# digital_interface_1_1.net
KiCad netlist of a schematic drawn in EAGLE
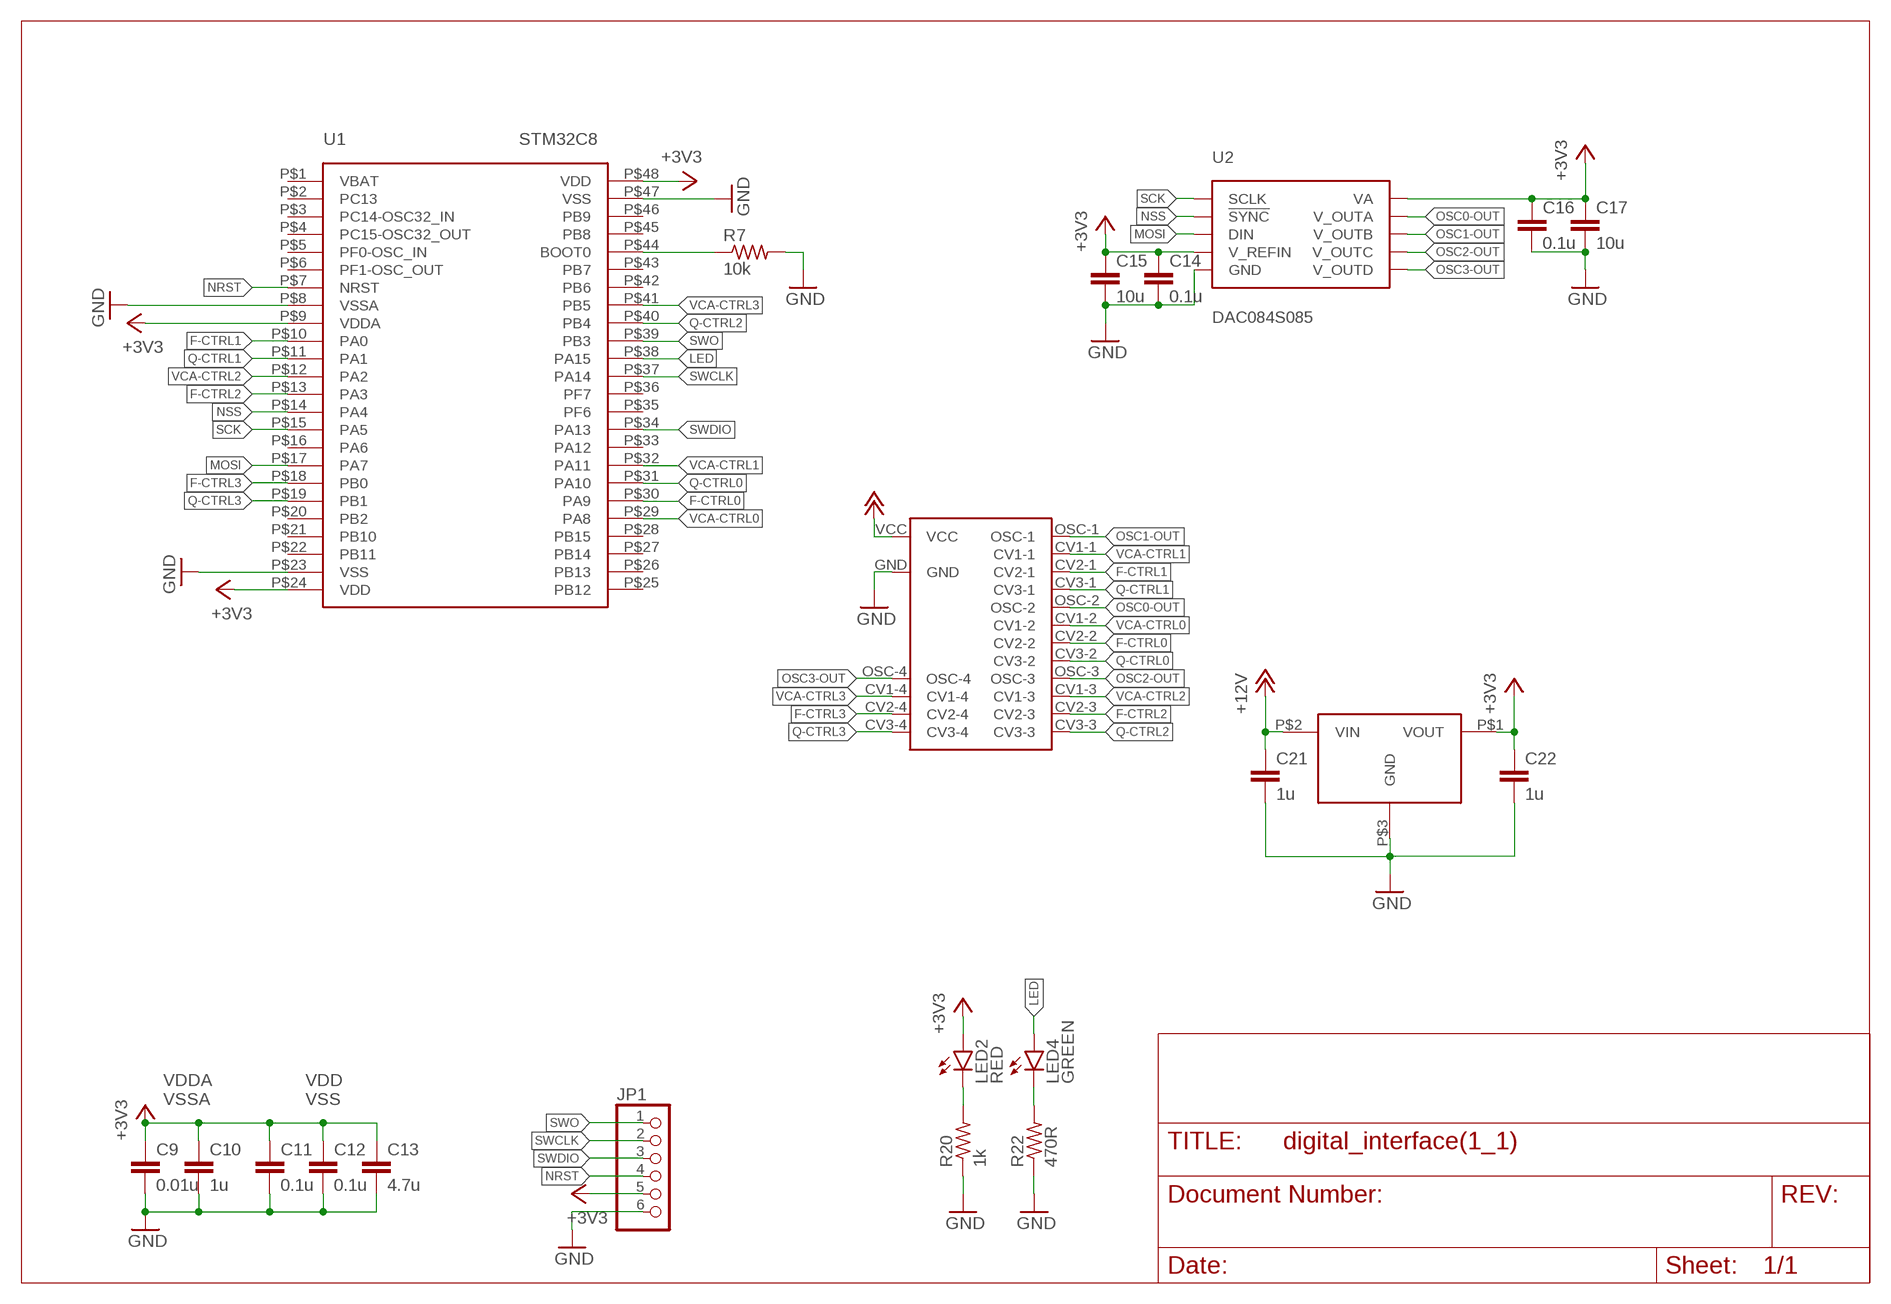
[diagram p0: schematic, sheet 1]

(export (version "E")
  (design (tool "Eeschema 10.0.6"))
  (components
    (comp (ref "C9")
      (value "0.01u")
      (footprint "eagle-import:C0603")
      (libsource (lib "eagle-import") (part "C-EUC0603"))
    )
    (comp (ref "C10")
      (value "1u")
      (footprint "eagle-import:C0603")
      (libsource (lib "eagle-import") (part "C-EUC0603"))
    )
    (comp (ref "C11")
      (value "0.1u")
      (footprint "eagle-import:C0603")
      (libsource (lib "eagle-import") (part "C-EUC0603"))
    )
    (comp (ref "C12")
      (value "0.1u")
      (footprint "eagle-import:C0603")
      (libsource (lib "eagle-import") (part "C-EUC0603"))
    )
    (comp (ref "C13")
      (value "4.7u")
      (footprint "eagle-import:C0603")
      (libsource (lib "eagle-import") (part "C-EUC0603"))
    )
    (comp (ref "C14")
      (value "0.1u")
      (footprint "eagle-import:C0603")
      (libsource (lib "eagle-import") (part "C-EUC0603"))
    )
    (comp (ref "C15")
      (value "10u")
      (footprint "eagle-import:C0603")
      (libsource (lib "eagle-import") (part "C-EUC0603"))
    )
    (comp (ref "C16")
      (value "0.1u")
      (footprint "eagle-import:C0603")
      (libsource (lib "eagle-import") (part "C-EUC0603"))
    )
    (comp (ref "C17")
      (value "10u")
      (footprint "eagle-import:C0603")
      (libsource (lib "eagle-import") (part "C-EUC0603"))
    )
    (comp (ref "C21")
      (value "1u")
      (footprint "eagle-import:C0603")
      (libsource (lib "eagle-import") (part "C-EUC0603"))
    )
    (comp (ref "C22")
      (value "1u")
      (footprint "eagle-import:C0603")
      (libsource (lib "eagle-import") (part "C-EUC0603"))
    )
    (comp (ref "JP1")
      (value "PINHD-1X6")
      (footprint "eagle-import:1X06")
      (libsource (lib "eagle-import") (part "PINHD-1X6"))
    )
    (comp (ref "LED2")
      (value "RED")
      (footprint "eagle-import:1206")
      (libsource (lib "eagle-import") (part "LEDSMT1206"))
    )
    (comp (ref "LED4")
      (value "GREEN")
      (footprint "eagle-import:1206")
      (libsource (lib "eagle-import") (part "LEDSMT1206"))
    )
    (comp (ref "R7")
      (value "10k")
      (footprint "eagle-import:R0603")
      (libsource (lib "eagle-import") (part "R-US_R0603"))
    )
    (comp (ref "R20")
      (value "1k")
      (footprint "eagle-import:R0603")
      (libsource (lib "eagle-import") (part "R-US_R0603"))
    )
    (comp (ref "R22")
      (value "470R")
      (footprint "eagle-import:R0603")
      (libsource (lib "eagle-import") (part "R-US_R0603"))
    )
    (comp (ref "U$1")
      (value "CV_MODULE")
      (footprint "eagle-import:CV_MODULE")
      (libsource (lib "eagle-import") (part "CV_MODULE"))
    )
    (comp (ref "U1")
      (value "STM32C8")
      (footprint "eagle-import:LQFP48")
      (libsource (lib "eagle-import") (part "STM32C8"))
    )
    (comp (ref "U2")
      (value "DAC084S085")
      (footprint "eagle-import:VSSOP10")
      (libsource (lib "eagle-import") (part "DAC084S085"))
    )
    (comp (ref "U3")
      (value "TLV760")
      (footprint "eagle-import:SOT23-3")
      (libsource (lib "eagle-import") (part "TLV760"))
    )
  )
  (nets
    (net (code "1") (name "+3V3") (class "Default")
      (node (ref "C10") (pin "1") (pinfunction "1_1") (pintype "passive"))
      (node (ref "C11") (pin "1") (pinfunction "1_1") (pintype "passive"))
      (node (ref "C12") (pin "1") (pinfunction "1_1") (pintype "passive"))
      (node (ref "C13") (pin "1") (pinfunction "1_1") (pintype "passive"))
      (node (ref "C14") (pin "1") (pinfunction "1_1") (pintype "passive"))
      (node (ref "C15") (pin "1") (pinfunction "1_1") (pintype "passive"))
      (node (ref "C16") (pin "1") (pinfunction "1_1") (pintype "passive"))
      (node (ref "C17") (pin "1") (pinfunction "1_1") (pintype "passive"))
      (node (ref "C22") (pin "1") (pinfunction "1_1") (pintype "passive"))
      (node (ref "C9") (pin "1") (pinfunction "1_1") (pintype "passive"))
      (node (ref "JP1") (pin "5") (pinfunction "5_5") (pintype "passive"))
      (node (ref "LED2") (pin "A") (pinfunction "A_A") (pintype "passive"))
      (node (ref "U1") (pin "P$24") (pinfunction "VDD_P$24") (pintype "bidirectional"))
      (node (ref "U1") (pin "P$48") (pinfunction "VDD_P$48") (pintype "bidirectional"))
      (node (ref "U1") (pin "P$9") (pinfunction "VDDA_P$9") (pintype "bidirectional"))
      (node (ref "U2") (pin "P$1") (pinfunction "VA_P$1") (pintype "bidirectional"))
      (node (ref "U2") (pin "P$7") (pinfunction "V_REFIN_P$7") (pintype "bidirectional"))
      (node (ref "U3") (pin "P$1") (pinfunction "VOUT_P$1") (pintype "bidirectional"))
    )
    (net (code "2") (name "+12V") (class "Default")
      (node (ref "C21") (pin "1") (pinfunction "1_1") (pintype "passive"))
      (node (ref "U$1") (pin "VCC") (pinfunction "VCC_VCC") (pintype "bidirectional"))
      (node (ref "U3") (pin "P$2") (pinfunction "VIN_P$2") (pintype "bidirectional"))
    )
    (net (code "3") (name "F-CTRL0") (class "Default")
      (node (ref "U$1") (pin "CV2-2") (pinfunction "CV2-2_CV2-2") (pintype "bidirectional"))
      (node (ref "U1") (pin "P$30") (pinfunction "PA9_P$30") (pintype "bidirectional"))
    )
    (net (code "4") (name "F-CTRL1") (class "Default")
      (node (ref "U$1") (pin "CV2-1") (pinfunction "CV2-1_CV2-1") (pintype "bidirectional"))
      (node (ref "U1") (pin "P$10") (pinfunction "PA0_P$10") (pintype "bidirectional"))
    )
    (net (code "5") (name "F-CTRL2") (class "Default")
      (node (ref "U$1") (pin "CV2-3") (pinfunction "CV2-3_CV2-3") (pintype "bidirectional"))
      (node (ref "U1") (pin "P$13") (pinfunction "PA3_P$13") (pintype "bidirectional"))
    )
    (net (code "6") (name "F-CTRL3") (class "Default")
      (node (ref "U$1") (pin "CV2-4") (pinfunction "CV2-4_CV2-4") (pintype "bidirectional"))
      (node (ref "U1") (pin "P$18") (pinfunction "PB0_P$18") (pintype "bidirectional"))
    )
    (net (code "7") (name "GND") (class "Default")
      (node (ref "C10") (pin "2") (pinfunction "2_2") (pintype "passive"))
      (node (ref "C11") (pin "2") (pinfunction "2_2") (pintype "passive"))
      (node (ref "C12") (pin "2") (pinfunction "2_2") (pintype "passive"))
      (node (ref "C13") (pin "2") (pinfunction "2_2") (pintype "passive"))
      (node (ref "C14") (pin "2") (pinfunction "2_2") (pintype "passive"))
      (node (ref "C15") (pin "2") (pinfunction "2_2") (pintype "passive"))
      (node (ref "C16") (pin "2") (pinfunction "2_2") (pintype "passive"))
      (node (ref "C17") (pin "2") (pinfunction "2_2") (pintype "passive"))
      (node (ref "C21") (pin "2") (pinfunction "2_2") (pintype "passive"))
      (node (ref "C22") (pin "2") (pinfunction "2_2") (pintype "passive"))
      (node (ref "C9") (pin "2") (pinfunction "2_2") (pintype "passive"))
      (node (ref "JP1") (pin "6") (pinfunction "6_6") (pintype "passive"))
      (node (ref "R20") (pin "1") (pinfunction "1_1") (pintype "passive"))
      (node (ref "R22") (pin "1") (pinfunction "1_1") (pintype "passive"))
      (node (ref "R7") (pin "2") (pinfunction "2_2") (pintype "passive"))
      (node (ref "U$1") (pin "GND") (pinfunction "GND_GND") (pintype "bidirectional"))
      (node (ref "U1") (pin "P$23") (pinfunction "VSS_P$23") (pintype "bidirectional"))
      (node (ref "U1") (pin "P$47") (pinfunction "VSS_P$47") (pintype "bidirectional"))
      (node (ref "U1") (pin "P$8") (pinfunction "VSSA_P$8") (pintype "bidirectional"))
      (node (ref "U2") (pin "P$6") (pinfunction "GND_P$6") (pintype "bidirectional"))
      (node (ref "U3") (pin "P$3") (pinfunction "GND_P$3") (pintype "bidirectional"))
    )
    (net (code "8") (name "LED") (class "Default")
      (node (ref "LED4") (pin "A") (pinfunction "A_A") (pintype "passive"))
      (node (ref "U1") (pin "P$38") (pinfunction "PA15_P$38") (pintype "bidirectional"))
    )
    (net (code "9") (name "MOSI") (class "Default")
      (node (ref "U1") (pin "P$17") (pinfunction "PA7_P$17") (pintype "bidirectional"))
      (node (ref "U2") (pin "P$8") (pinfunction "DIN_P$8") (pintype "bidirectional"))
    )
    (net (code "10") (name "NRST") (class "Default")
      (node (ref "JP1") (pin "4") (pinfunction "4_4") (pintype "passive"))
      (node (ref "U1") (pin "P$7") (pinfunction "NRST_P$7") (pintype "bidirectional"))
    )
    (net (code "11") (name "NSS") (class "Default")
      (node (ref "U1") (pin "P$14") (pinfunction "PA4_P$14") (pintype "bidirectional"))
      (node (ref "U2") (pin "P$9") (pinfunction "~{SYNC}_P$9") (pintype "bidirectional"))
    )
    (net (code "12") (name "Net-(LED2-PadC)") (class "Default")
      (node (ref "LED2") (pin "C") (pinfunction "C_C") (pintype "passive"))
      (node (ref "R20") (pin "2") (pinfunction "2_2") (pintype "passive"))
    )
    (net (code "13") (name "Net-(LED4-PadC)") (class "Default")
      (node (ref "LED4") (pin "C") (pinfunction "C_C") (pintype "passive"))
      (node (ref "R22") (pin "2") (pinfunction "2_2") (pintype "passive"))
    )
    (net (code "14") (name "Net-(U1-BOOT0)") (class "Default")
      (node (ref "R7") (pin "1") (pinfunction "1_1") (pintype "passive"))
      (node (ref "U1") (pin "P$44") (pinfunction "BOOT0_P$44") (pintype "bidirectional"))
    )
    (net (code "15") (name "OSC0-OUT") (class "Default")
      (node (ref "U$1") (pin "OSC-2") (pinfunction "OSC-2_OSC-2") (pintype "bidirectional"))
      (node (ref "U2") (pin "P$2") (pinfunction "V_OUTA_P$2") (pintype "bidirectional"))
    )
    (net (code "16") (name "OSC1-OUT") (class "Default")
      (node (ref "U$1") (pin "OSC-1") (pinfunction "OSC-1_OSC-1") (pintype "bidirectional"))
      (node (ref "U2") (pin "P$3") (pinfunction "V_OUTB_P$3") (pintype "bidirectional"))
    )
    (net (code "17") (name "OSC2-OUT") (class "Default")
      (node (ref "U$1") (pin "OSC-3") (pinfunction "OSC-3_OSC-3") (pintype "bidirectional"))
      (node (ref "U2") (pin "P$4") (pinfunction "V_OUTC_P$4") (pintype "bidirectional"))
    )
    (net (code "18") (name "OSC3-OUT") (class "Default")
      (node (ref "U$1") (pin "OSC-4") (pinfunction "OSC-4_OSC-4") (pintype "bidirectional"))
      (node (ref "U2") (pin "P$5") (pinfunction "V_OUTD_P$5") (pintype "bidirectional"))
    )
    (net (code "19") (name "Q-CTRL0") (class "Default")
      (node (ref "U$1") (pin "CV3-2") (pinfunction "CV3-2_CV3-2") (pintype "bidirectional"))
      (node (ref "U1") (pin "P$31") (pinfunction "PA10_P$31") (pintype "bidirectional"))
    )
    (net (code "20") (name "Q-CTRL1") (class "Default")
      (node (ref "U$1") (pin "CV3-1") (pinfunction "CV3-1_CV3-1") (pintype "bidirectional"))
      (node (ref "U1") (pin "P$11") (pinfunction "PA1_P$11") (pintype "bidirectional"))
    )
    (net (code "21") (name "Q-CTRL2") (class "Default")
      (node (ref "U$1") (pin "CV3-3") (pinfunction "CV3-3_CV3-3") (pintype "bidirectional"))
      (node (ref "U1") (pin "P$40") (pinfunction "PB4_P$40") (pintype "bidirectional"))
    )
    (net (code "22") (name "Q-CTRL3") (class "Default")
      (node (ref "U$1") (pin "CV3-4") (pinfunction "CV3-4_CV3-4") (pintype "bidirectional"))
      (node (ref "U1") (pin "P$19") (pinfunction "PB1_P$19") (pintype "bidirectional"))
    )
    (net (code "23") (name "SCK") (class "Default")
      (node (ref "U1") (pin "P$15") (pinfunction "PA5_P$15") (pintype "bidirectional"))
      (node (ref "U2") (pin "P$10") (pinfunction "SCLK_P$10") (pintype "bidirectional"))
    )
    (net (code "24") (name "SWCLK") (class "Default")
      (node (ref "JP1") (pin "2") (pinfunction "2_2") (pintype "passive"))
      (node (ref "U1") (pin "P$37") (pinfunction "PA14_P$37") (pintype "bidirectional"))
    )
    (net (code "25") (name "SWDIO") (class "Default")
      (node (ref "JP1") (pin "3") (pinfunction "3_3") (pintype "passive"))
      (node (ref "U1") (pin "P$34") (pinfunction "PA13_P$34") (pintype "bidirectional"))
    )
    (net (code "26") (name "SWO") (class "Default")
      (node (ref "JP1") (pin "1") (pinfunction "1_1") (pintype "passive"))
      (node (ref "U1") (pin "P$39") (pinfunction "PB3_P$39") (pintype "bidirectional"))
    )
    (net (code "27") (name "VCA-CTRL0") (class "Default")
      (node (ref "U$1") (pin "CV1-2") (pinfunction "CV1-2_CV1-2") (pintype "bidirectional"))
      (node (ref "U1") (pin "P$29") (pinfunction "PA8_P$29") (pintype "bidirectional"))
    )
    (net (code "28") (name "VCA-CTRL1") (class "Default")
      (node (ref "U$1") (pin "CV1-1") (pinfunction "CV1-1_CV1-1") (pintype "bidirectional"))
      (node (ref "U1") (pin "P$32") (pinfunction "PA11_P$32") (pintype "bidirectional"))
    )
    (net (code "29") (name "VCA-CTRL2") (class "Default")
      (node (ref "U$1") (pin "CV1-3") (pinfunction "CV1-3_CV1-3") (pintype "bidirectional"))
      (node (ref "U1") (pin "P$12") (pinfunction "PA2_P$12") (pintype "bidirectional"))
    )
    (net (code "30") (name "VCA-CTRL3") (class "Default")
      (node (ref "U$1") (pin "CV1-4") (pinfunction "CV1-4_CV1-4") (pintype "bidirectional"))
      (node (ref "U1") (pin "P$41") (pinfunction "PB5_P$41") (pintype "bidirectional"))
    )
    (net (code "31") (name "unconnected-(U1-PA6-PadP$16)") (class "Default")
      (node (ref "U1") (pin "P$16") (pinfunction "PA6_P$16") (pintype "bidirectional"))
    )
    (net (code "32") (name "unconnected-(U1-PA12-PadP$33)") (class "Default")
      (node (ref "U1") (pin "P$33") (pinfunction "PA12_P$33") (pintype "bidirectional"))
    )
    (net (code "33") (name "unconnected-(U1-PB2-PadP$20)") (class "Default")
      (node (ref "U1") (pin "P$20") (pinfunction "PB2_P$20") (pintype "bidirectional"))
    )
    (net (code "34") (name "unconnected-(U1-PB6-PadP$42)") (class "Default")
      (node (ref "U1") (pin "P$42") (pinfunction "PB6_P$42") (pintype "bidirectional"))
    )
    (net (code "35") (name "unconnected-(U1-PB7-PadP$43)") (class "Default")
      (node (ref "U1") (pin "P$43") (pinfunction "PB7_P$43") (pintype "bidirectional"))
    )
    (net (code "36") (name "unconnected-(U1-PB8-PadP$45)") (class "Default")
      (node (ref "U1") (pin "P$45") (pinfunction "PB8_P$45") (pintype "bidirectional"))
    )
    (net (code "37") (name "unconnected-(U1-PB9-PadP$46)") (class "Default")
      (node (ref "U1") (pin "P$46") (pinfunction "PB9_P$46") (pintype "bidirectional"))
    )
    (net (code "38") (name "unconnected-(U1-PB10-PadP$21)") (class "Default")
      (node (ref "U1") (pin "P$21") (pinfunction "PB10_P$21") (pintype "bidirectional"))
    )
    (net (code "39") (name "unconnected-(U1-PB11-PadP$22)") (class "Default")
      (node (ref "U1") (pin "P$22") (pinfunction "PB11_P$22") (pintype "bidirectional"))
    )
    (net (code "40") (name "unconnected-(U1-PB12-PadP$25)") (class "Default")
      (node (ref "U1") (pin "P$25") (pinfunction "PB12_P$25") (pintype "bidirectional"))
    )
    (net (code "41") (name "unconnected-(U1-PB13-PadP$26)") (class "Default")
      (node (ref "U1") (pin "P$26") (pinfunction "PB13_P$26") (pintype "bidirectional"))
    )
    (net (code "42") (name "unconnected-(U1-PB14-PadP$27)") (class "Default")
      (node (ref "U1") (pin "P$27") (pinfunction "PB14_P$27") (pintype "bidirectional"))
    )
    (net (code "43") (name "unconnected-(U1-PB15-PadP$28)") (class "Default")
      (node (ref "U1") (pin "P$28") (pinfunction "PB15_P$28") (pintype "bidirectional"))
    )
    (net (code "44") (name "unconnected-(U1-PC13-PadP$2)") (class "Default")
      (node (ref "U1") (pin "P$2") (pinfunction "PC13_P$2") (pintype "bidirectional"))
    )
    (net (code "45") (name "unconnected-(U1-PC14-OSC32_IN-PadP$3)") (class "Default")
      (node (ref "U1") (pin "P$3") (pinfunction "PC14-OSC32_IN_P$3") (pintype "bidirectional"))
    )
    (net (code "46") (name "unconnected-(U1-PC15-OSC32_OUT-PadP$4)") (class "Default")
      (node (ref "U1") (pin "P$4") (pinfunction "PC15-OSC32_OUT_P$4") (pintype "bidirectional"))
    )
    (net (code "47") (name "unconnected-(U1-PF0-OSC_IN-PadP$5)") (class "Default")
      (node (ref "U1") (pin "P$5") (pinfunction "PF0-OSC_IN_P$5") (pintype "bidirectional"))
    )
    (net (code "48") (name "unconnected-(U1-PF1-OSC_OUT-PadP$6)") (class "Default")
      (node (ref "U1") (pin "P$6") (pinfunction "PF1-OSC_OUT_P$6") (pintype "bidirectional"))
    )
    (net (code "49") (name "unconnected-(U1-PF6-PadP$35)") (class "Default")
      (node (ref "U1") (pin "P$35") (pinfunction "PF6_P$35") (pintype "bidirectional"))
    )
    (net (code "50") (name "unconnected-(U1-PF7-PadP$36)") (class "Default")
      (node (ref "U1") (pin "P$36") (pinfunction "PF7_P$36") (pintype "bidirectional"))
    )
    (net (code "51") (name "unconnected-(U1-VBAT-PadP$1)") (class "Default")
      (node (ref "U1") (pin "P$1") (pinfunction "VBAT_P$1") (pintype "bidirectional"))
    )
  )
)
